# DC_MOTOR_DRIVER_V2_0.net
KiCad netlist of a schematic drawn in EasyEDA Pro
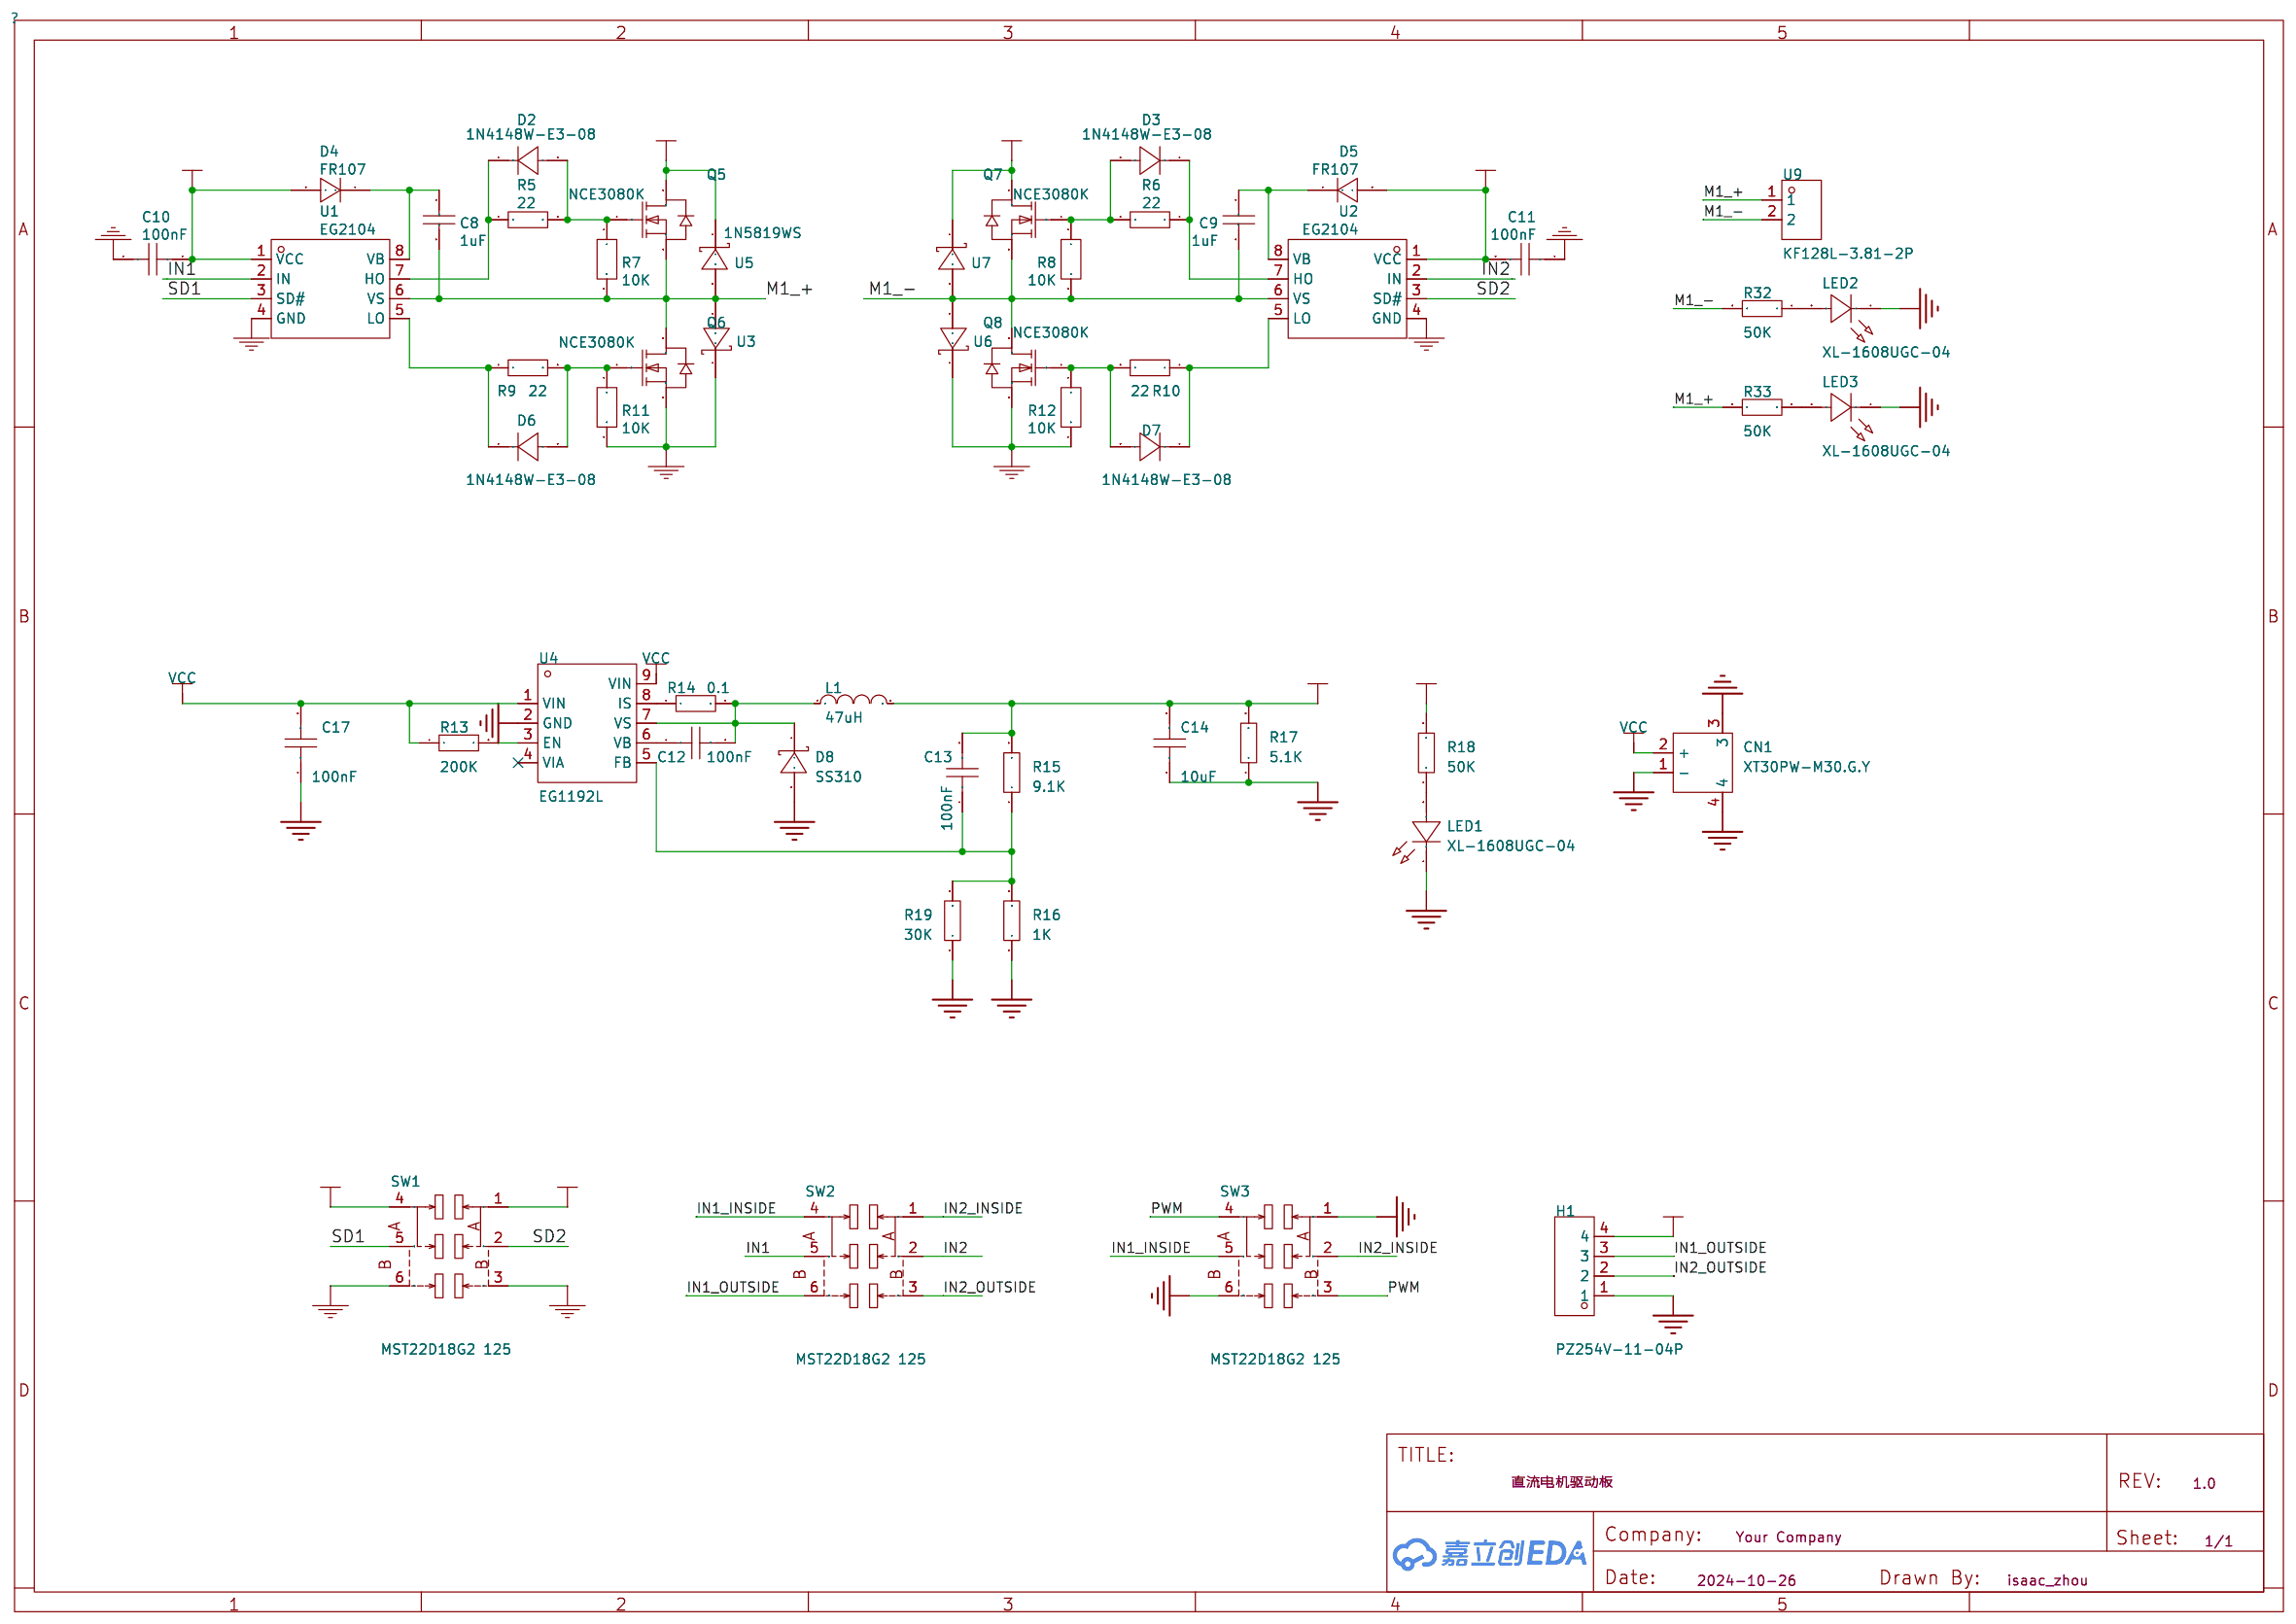
[diagram p0: Sheet_1]
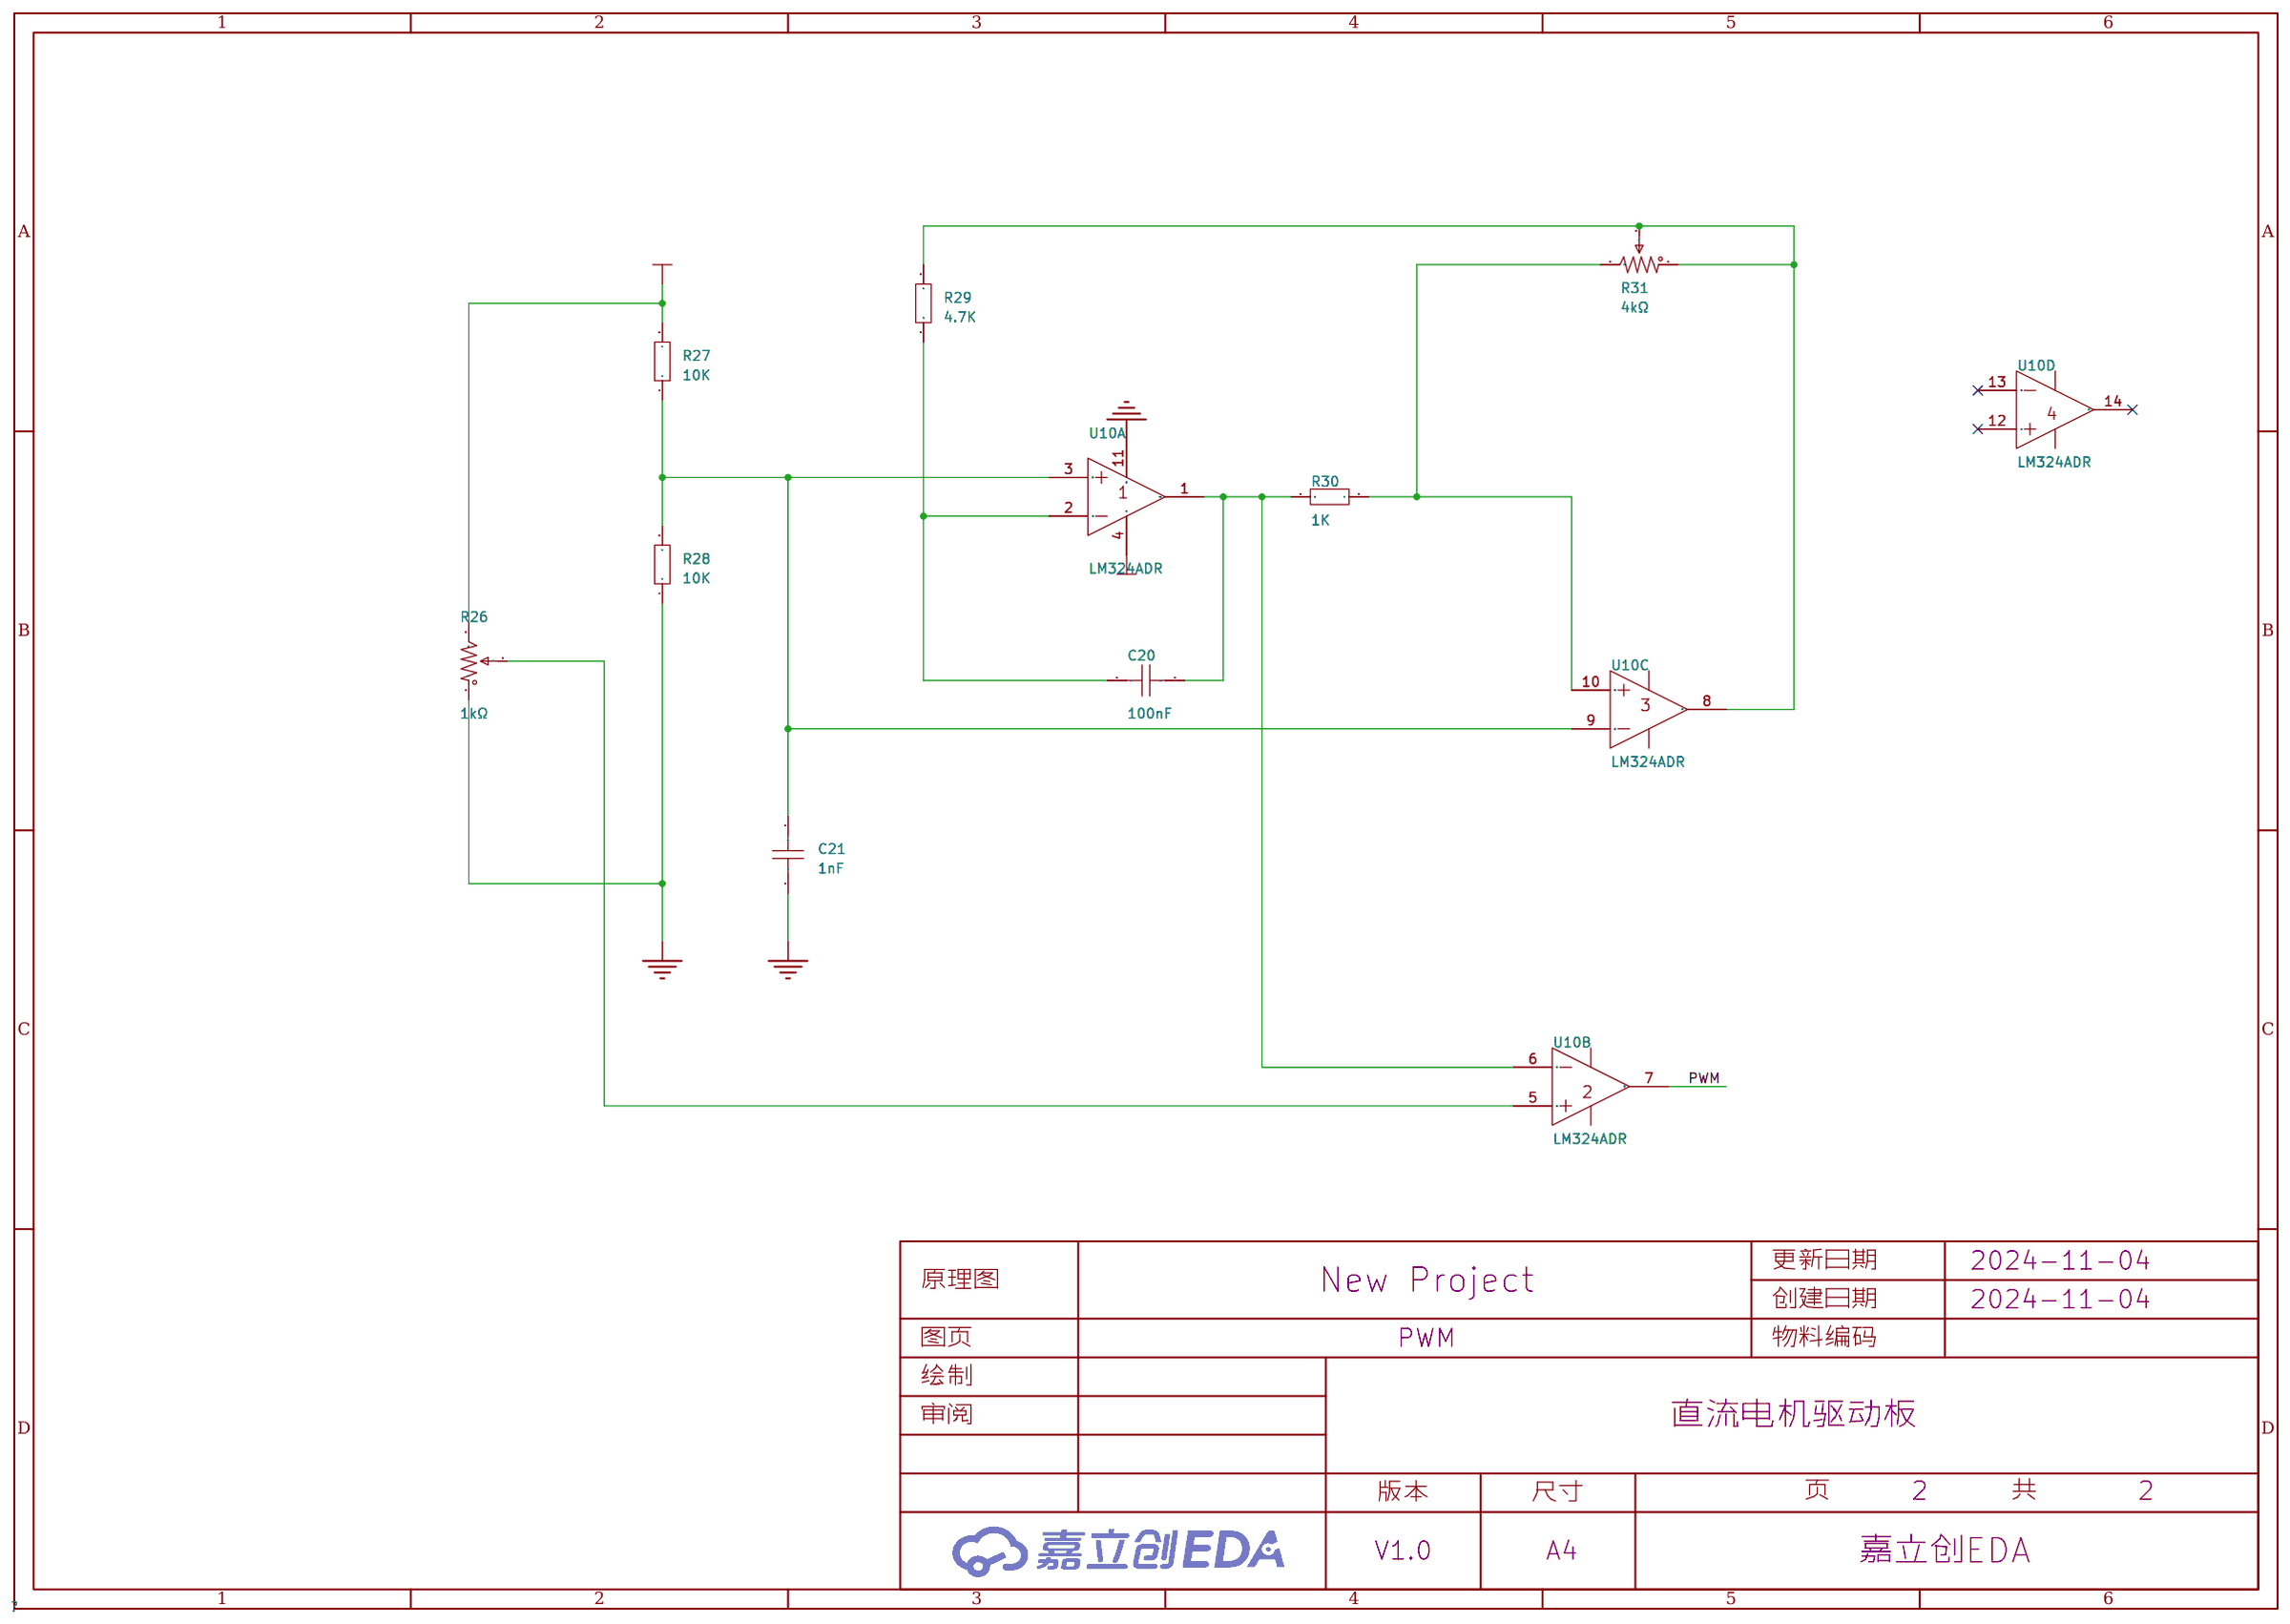
[diagram p1: PWM]

(export (version "E")
  (design (tool "Eeschema 10.0.6"))
  (components
    (comp (ref "C8")
      (value "1uF")
      (fields (field (name "Manufacturer Part") "CL21F105ZOFNNNE") (field (name "Manufacturer") "SAMSUNG"))
      (libsource (lib "easyedapro") (part "1uF"))
    )
    (comp (ref "C9")
      (value "1uF")
      (fields (field (name "Manufacturer Part") "CL21F105ZOFNNNE") (field (name "Manufacturer") "SAMSUNG"))
      (libsource (lib "easyedapro") (part "1uF"))
    )
    (comp (ref "C10")
      (value "100nF")
      (fields (field (name "Manufacturer Part") "C0805C104K4RAC7800") (field (name "Manufacturer") "KEMET"))
      (libsource (lib "") (part "100nF_1"))
    )
    (comp (ref "C11")
      (value "100nF")
      (fields (field (name "Manufacturer Part") "C0805C104K4RAC7800") (field (name "Manufacturer") "KEMET"))
      (libsource (lib "easyedapro") (part "100nF"))
    )
    (comp (ref "C12")
      (value "100nF")
      (footprint "easyedapro:C0603")
      (libsource (lib "easyedapro") (part "CapAcitance"))
    )
    (comp (ref "C13")
      (value "100nF")
      (footprint "easyedapro:C0603")
      (libsource (lib "easyedapro") (part "CapAcitance"))
    )
    (comp (ref "C14")
      (value "10uF")
      (footprint "easyedapro:C0603")
      (libsource (lib "easyedapro") (part "CapAcitance"))
    )
    (comp (ref "C17")
      (value "100nF")
      (footprint "easyedapro:C0603")
      (libsource (lib "easyedapro") (part "CapAcitance"))
    )
    (comp (ref "CN1")
      (value "XT30PW-M30.G.Y")
      (footprint "easyedapro:CONN-TH_XT30PW-M")
      (description "类别:-;类型1:-;")
      (fields (field (name "Manufacturer") "AMASS(艾迈斯)"))
      (libsource (lib "easyedapro") (part "XT30PW-M"))
    )
    (comp (ref "D2")
      (value "1N4148W-E3-08")
      (fields (field (name "Manufacturer") "VISHAY(威世)"))
      (libsource (lib "easyedapro") (part "1N4148W_C727110"))
    )
    (comp (ref "D3")
      (value "1N4148W-E3-08")
      (fields (field (name "Manufacturer") "VISHAY(威世)"))
      (libsource (lib "") (part "1N4148W_C727110_1"))
    )
    (comp (ref "D4")
      (value "FR107")
      (fields (field (name "Manufacturer") "Slkor(萨科微)"))
      (libsource (lib "") (part "FR107_C511885_1"))
    )
    (comp (ref "D5")
      (value "FR107")
      (fields (field (name "Manufacturer") "Slkor(萨科微)"))
      (libsource (lib "easyedapro") (part "FR107_C511885"))
    )
    (comp (ref "D6")
      (value "1N4148W-E3-08")
      (fields (field (name "Manufacturer") "VISHAY(威世)"))
      (libsource (lib "easyedapro") (part "1N4148W_C727110"))
    )
    (comp (ref "D7")
      (value "1N4148W-E3-08")
      (fields (field (name "Manufacturer") "VISHAY(威世)"))
      (libsource (lib "") (part "1N4148W_C727110_1"))
    )
    (comp (ref "D8")
      (value "SS310")
      (footprint "easyedapro:SMA_L4.3-W2.6-LS5.2-RD")
      (description "二极管配置:独立式;正向压降(Vf):850mV@3A;直流反向耐压(Vr):100V;整流电流:3A;")
      (fields (field (name "Manufacturer") "MDD(辰达半导体)"))
      (libsource (lib "easyedapro") (part "SS310"))
    )
    (comp (ref "H1")
      (value "PZ254V-11-04P")
      (footprint "easyedapro:HDR-TH_4P-P2.54-V-M")
      (fields (field (name "Manufacturer") "XFCN(兴飞)"))
      (libsource (lib "easyedapro") (part "PZ254V-11-04P_C2691448"))
    )
    (comp (ref "L1")
      (value "47uH")
      (fields (field (name "Manufacturer Part") "CKST0603-47uH/M") (field (name "Manufacturer") "CENKER(岑科)"))
      (libsource (lib "easyedapro") (part "SDFL1608S100KTF"))
    )
    (comp (ref "LED1")
      (value "XL-1608UGC-04")
      (footprint "easyedapro:LED0603-RD_GREEN")
      (fields (field (name "Manufacturer") "XINGLIGHT(成兴光)"))
      (libsource (lib "easyedapro") (part "XL-1608UGC-04"))
    )
    (comp (ref "LED2")
      (value "XL-1608UGC-04")
      (footprint "easyedapro:LED0603-RD_GREEN")
      (fields (field (name "Manufacturer") "XINGLIGHT(成兴光)"))
      (libsource (lib "easyedapro") (part "XL-1608UGC-04"))
    )
    (comp (ref "LED3")
      (value "XL-1608UGC-04")
      (footprint "easyedapro:LED0603-RD_GREEN")
      (fields (field (name "Manufacturer") "XINGLIGHT(成兴光)"))
      (libsource (lib "easyedapro") (part "XL-1608UGC-04"))
    )
    (comp (ref "Q5")
      (value "NCE3080K")
      (footprint "easyedapro:TO-252-2_L6.6-W6.1-P4.57-LS9.9-TL-CW")
      (fields (field (name "Manufacturer") "NCE(无锡新洁能)"))
      (libsource (lib "easyedapro") (part "NCE3080K"))
    )
    (comp (ref "Q6")
      (value "NCE3080K")
      (footprint "easyedapro:TO-252-2_L6.6-W6.1-P4.57-LS9.9-TL-CW")
      (fields (field (name "Manufacturer") "NCE(无锡新洁能)"))
      (libsource (lib "easyedapro") (part "NCE3080K"))
    )
    (comp (ref "Q7")
      (value "NCE3080K")
      (footprint "easyedapro:TO-252-2_L6.6-W6.1-P4.57-LS9.9-TL-CW")
      (fields (field (name "Manufacturer") "NCE(无锡新洁能)"))
      (libsource (lib "easyedapro") (part "NCE3080K"))
    )
    (comp (ref "Q8")
      (value "NCE3080K")
      (footprint "easyedapro:TO-252-2_L6.6-W6.1-P4.57-LS9.9-TL-CW")
      (fields (field (name "Manufacturer") "NCE(无锡新洁能)"))
      (libsource (lib "easyedapro") (part "NCE3080K"))
    )
    (comp (ref "R5")
      (value "22")
      (fields (field (name "Manufacturer Part") "0805W8F220JT5E") (field (name "Manufacturer") "UniOhm"))
      (libsource (lib "easyedapro") (part "22"))
    )
    (comp (ref "R6")
      (value "22")
      (fields (field (name "Manufacturer Part") "0805W8F220JT5E") (field (name "Manufacturer") "UniOhm"))
      (libsource (lib "") (part "22_1"))
    )
    (comp (ref "R7")
      (value "10K")
      (fields
        (field (name "Manufacturer Part") "0805W8F1002T5E")
        (field (name "Manufacturer") "Uniroyal Elec")
      )
      (libsource (lib "easyedapro") (part "10K"))
    )
    (comp (ref "R8")
      (value "10K")
      (fields
        (field (name "Manufacturer Part") "0805W8F1002T5E")
        (field (name "Manufacturer") "Uniroyal Elec")
      )
      (libsource (lib "easyedapro") (part "10K"))
    )
    (comp (ref "R9")
      (value "22")
      (fields (field (name "Manufacturer Part") "0805W8F220JT5E") (field (name "Manufacturer") "UniOhm"))
      (libsource (lib "easyedapro") (part "22"))
    )
    (comp (ref "R10")
      (value "22")
      (fields (field (name "Manufacturer Part") "0805W8F220JT5E") (field (name "Manufacturer") "UniOhm"))
      (libsource (lib "") (part "22_1"))
    )
    (comp (ref "R11")
      (value "10K")
      (fields
        (field (name "Manufacturer Part") "0805W8F1002T5E")
        (field (name "Manufacturer") "Uniroyal Elec")
      )
      (libsource (lib "easyedapro") (part "10K"))
    )
    (comp (ref "R12")
      (value "10K")
      (fields
        (field (name "Manufacturer Part") "0805W8F1002T5E")
        (field (name "Manufacturer") "Uniroyal Elec")
      )
      (libsource (lib "easyedapro") (part "10K"))
    )
    (comp (ref "R13")
      (value "200K")
      (footprint "easyedapro:R0603")
      (libsource (lib "easyedapro") (part "电阻"))
    )
    (comp (ref "R14") (value "0.1") (footprint "easyedapro:R0603") (libsource (lib "easyedapro") (part "电阻")))
    (comp (ref "R15")
      (value "9.1K")
      (footprint "easyedapro:R0603")
      (libsource (lib "easyedapro") (part "电阻"))
    )
    (comp (ref "R16") (value "1K") (footprint "easyedapro:R0603") (libsource (lib "easyedapro") (part "电阻")))
    (comp (ref "R17")
      (value "5.1K")
      (footprint "easyedapro:R0603")
      (libsource (lib "easyedapro") (part "电阻"))
    )
    (comp (ref "R18") (value "50K") (footprint "easyedapro:R0603") (libsource (lib "easyedapro") (part "电阻")))
    (comp (ref "R19") (value "30K") (footprint "easyedapro:R0603") (libsource (lib "easyedapro") (part "电阻")))
    (comp (ref "R32") (value "50K") (footprint "easyedapro:R0603") (libsource (lib "easyedapro") (part "电阻")))
    (comp (ref "R33") (value "50K") (footprint "easyedapro:R0603") (libsource (lib "easyedapro") (part "电阻")))
    (comp (ref "SW1")
      (value "MST22D18G2 125")
      (footprint "easyedapro:SW-SMD_MST22D18G2")
      (description "电路结构:双刀双掷;安装方式:立贴;开关颜色:黑色;额定电流(DC):100mA;额定电压(DC):12V;机械寿命:1万次;")
      (fields (field (name "Manufacturer") "SHOU HAN(首韩)"))
      (libsource (lib "easyedapro") (part "MST22D18G2 125"))
    )
    (comp (ref "SW2")
      (value "MST22D18G2 125")
      (footprint "easyedapro:SW-SMD_MST22D18G2")
      (description "电路结构:双刀双掷;安装方式:立贴;开关颜色:黑色;额定电流(DC):100mA;额定电压(DC):12V;机械寿命:1万次;")
      (fields (field (name "Manufacturer") "SHOU HAN(首韩)"))
      (libsource (lib "easyedapro") (part "MST22D18G2 125"))
    )
    (comp (ref "SW3")
      (value "MST22D18G2 125")
      (footprint "easyedapro:SW-SMD_MST22D18G2")
      (description "电路结构:双刀双掷;安装方式:立贴;开关颜色:黑色;额定电流(DC):100mA;额定电压(DC):12V;机械寿命:1万次;")
      (fields (field (name "Manufacturer") "SHOU HAN(首韩)"))
      (libsource (lib "easyedapro") (part "MST22D18G2 125"))
    )
    (comp (ref "U1")
      (value "EG2104")
      (fields (field (name "Manufacturer") "EG(屹晶微)"))
      (libsource (lib "") (part "EG2104_1"))
    )
    (comp (ref "U2")
      (value "EG2104")
      (fields (field (name "Manufacturer") "EG(屹晶微)"))
      (libsource (lib "easyedapro") (part "EG2104"))
    )
    (comp (ref "U3")
      (value "1N5819WS")
      (fields (field (name "Manufacturer") "Hottech(合科泰)"))
      (libsource (lib "easyedapro") (part "1N5819HW-MS"))
    )
    (comp (ref "U4")
      (value "EG1192L")
      (footprint "easyedapro:ESOP-8_L4.9-W3.9-P1.27-LS6.0-BL-EP")
      (description "零功耗使能降压 DCDC 电源芯片")
      (fields (field (name "Manufacturer") "EG(屹晶微)"))
      (libsource (lib "easyedapro") (part "EG1192L"))
    )
    (comp (ref "U5")
      (value "1N5819WS")
      (fields (field (name "Manufacturer") "Hottech(合科泰)"))
      (libsource (lib "easyedapro") (part "1N5819"))
    )
    (comp (ref "U6")
      (value "1N5819WS")
      (fields (field (name "Manufacturer") "Hottech(合科泰)"))
      (libsource (lib "easyedapro") (part "1N5819HW-MS"))
    )
    (comp (ref "U7")
      (value "1N5819WS")
      (fields (field (name "Manufacturer") "Hottech(合科泰)"))
      (libsource (lib "easyedapro") (part "1N5819HW-MS"))
    )
    (comp (ref "U9")
      (value "KF128L-3.81-2P")
      (footprint "easyedapro:CONN-TH_P3.81_KF128L-3.81-2P")
      (fields (field (name "Manufacturer") "KEFA(科发)"))
      (libsource (lib "easyedapro") (part "KF128L-3.81-2P"))
    )
    (comp (ref "C20")
      (value "100nF")
      (footprint "easyedapro:C0603")
      (libsource (lib "easyedapro") (part "CapAcitance"))
    )
    (comp (ref "C21")
      (value "1nF")
      (footprint "easyedapro:C0603")
      (libsource (lib "easyedapro") (part "CapAcitance"))
    )
    (comp (ref "R26")
      (value "1kΩ")
      (footprint "easyedapro:RES-ADJ-TH_3362P")
      (description "阻值:1kΩ;精度:±10%;")
      (fields (field (name "Manufacturer Part") "3362P-1-102") (field (name "Manufacturer") "BOCHEN(博晨)"))
      (libsource (lib "easyedapro") (part "3362P-1-102"))
    )
    (comp (ref "R27") (value "10K") (footprint "easyedapro:R0603") (libsource (lib "easyedapro") (part "电阻")))
    (comp (ref "R28") (value "10K") (footprint "easyedapro:R0603") (libsource (lib "easyedapro") (part "电阻")))
    (comp (ref "R29")
      (value "4.7K")
      (footprint "easyedapro:R0603")
      (libsource (lib "easyedapro") (part "电阻"))
    )
    (comp (ref "R30") (value "1K") (footprint "easyedapro:R0603") (libsource (lib "easyedapro") (part "电阻")))
    (comp (ref "R31")
      (value "4kΩ")
      (footprint "easyedapro:RES-ADJ-TH_3362P")
      (description "阻值:1kΩ;精度:±10%;")
      (fields (field (name "Manufacturer Part") "3362P-1-102") (field (name "Manufacturer") "BOCHEN(博晨)"))
      (libsource (lib "easyedapro") (part "3362P-1-102"))
    )
    (comp (ref "U10")
      (value "LM324ADR")
      (footprint "easyedapro:SOP-14_L8.6-W3.9-P1.27-LS6.0-BL")
      (fields (field (name "Manufacturer") "UMW(友台半导体)"))
      (libsource (lib "easyedapro") (part "LM324ADR_C2837469"))
    )
  )
  (nets
    (net (code "1") (name "12V") (class "Default")
      (node (ref "C10") (pin "2") (pinfunction "2_2") (pintype "unspecified"))
      (node (ref "C11") (pin "2") (pinfunction "2_2") (pintype "unspecified"))
      (node (ref "C13") (pin "2") (pinfunction "2_2") (pintype "input"))
      (node (ref "C14") (pin "2") (pinfunction "2_2") (pintype "input"))
      (node (ref "D4") (pin "2") (pinfunction "A_2") (pintype "unspecified"))
      (node (ref "D5") (pin "2") (pinfunction "A_2") (pintype "unspecified"))
      (node (ref "H1") (pin "4") (pinfunction "4_4") (pintype "unspecified"))
      (node (ref "L1") (pin "2") (pinfunction "2_2") (pintype "unspecified"))
      (node (ref "Q5") (pin "2") (pinfunction "D_2") (pintype "unspecified"))
      (node (ref "Q7") (pin "2") (pinfunction "D_2") (pintype "unspecified"))
      (node (ref "R15") (pin "2") (pinfunction "2_2") (pintype "input"))
      (node (ref "R17") (pin "2") (pinfunction "2_2") (pintype "input"))
      (node (ref "R18") (pin "2") (pinfunction "2_2") (pintype "input"))
      (node (ref "R26") (pin "3") (pinfunction "3_3") (pintype "unspecified"))
      (node (ref "R27") (pin "2") (pinfunction "2_2") (pintype "input"))
      (node (ref "SW1") (pin "1") (pinfunction "1_1") (pintype "unspecified"))
      (node (ref "SW1") (pin "4") (pinfunction "4_4") (pintype "unspecified"))
      (node (ref "U1") (pin "1") (pinfunction "VCC_1") (pintype "unspecified"))
      (node (ref "U10") (pin "4") (pinfunction "VCC_4") (pintype "unspecified"))
      (node (ref "U2") (pin "1") (pinfunction "VCC_1") (pintype "unspecified"))
      (node (ref "U5") (pin "1") (pinfunction "K_1") (pintype "unspecified"))
      (node (ref "U7") (pin "1") (pinfunction "K_1") (pintype "unspecified"))
    )
    (net (code "2") (name "GND") (class "Default")
      (node (ref "C10") (pin "1") (pinfunction "1_1") (pintype "unspecified"))
      (node (ref "C11") (pin "1") (pinfunction "1_1") (pintype "unspecified"))
      (node (ref "C14") (pin "1") (pinfunction "1_1") (pintype "input"))
      (node (ref "C17") (pin "1") (pinfunction "1_1") (pintype "input"))
      (node (ref "C21") (pin "1") (pinfunction "1_1") (pintype "input"))
      (node (ref "CN1") (pin "1") (pinfunction "-_1") (pintype "unspecified"))
      (node (ref "CN1") (pin "3") (pinfunction "3_3") (pintype "unspecified"))
      (node (ref "CN1") (pin "4") (pinfunction "4_4") (pintype "unspecified"))
      (node (ref "D8") (pin "2") (pinfunction "A_2") (pintype "unspecified"))
      (node (ref "H1") (pin "1") (pinfunction "1_1") (pintype "unspecified"))
      (node (ref "LED1") (pin "1") (pinfunction "K_1") (pintype "unspecified"))
      (node (ref "LED2") (pin "1") (pinfunction "K_1") (pintype "unspecified"))
      (node (ref "LED3") (pin "1") (pinfunction "K_1") (pintype "unspecified"))
      (node (ref "Q6") (pin "3") (pinfunction "S_3") (pintype "unspecified"))
      (node (ref "Q8") (pin "3") (pinfunction "S_3") (pintype "unspecified"))
      (node (ref "R11") (pin "2") (pinfunction "2_2") (pintype "unspecified"))
      (node (ref "R12") (pin "2") (pinfunction "2_2") (pintype "unspecified"))
      (node (ref "R16") (pin "1") (pinfunction "1_1") (pintype "input"))
      (node (ref "R17") (pin "1") (pinfunction "1_1") (pintype "input"))
      (node (ref "R19") (pin "1") (pinfunction "1_1") (pintype "input"))
      (node (ref "R26") (pin "1") (pinfunction "1_1") (pintype "unspecified"))
      (node (ref "R28") (pin "1") (pinfunction "1_1") (pintype "input"))
      (node (ref "SW1") (pin "3") (pinfunction "3_3") (pintype "unspecified"))
      (node (ref "SW1") (pin "6") (pinfunction "6_6") (pintype "unspecified"))
      (node (ref "SW3") (pin "1") (pinfunction "1_1") (pintype "unspecified"))
      (node (ref "SW3") (pin "6") (pinfunction "6_6") (pintype "unspecified"))
      (node (ref "U1") (pin "4") (pinfunction "GND_4") (pintype "unspecified"))
      (node (ref "U10") (pin "11") (pinfunction "GND_11") (pintype "unspecified"))
      (node (ref "U2") (pin "4") (pinfunction "GND_4") (pintype "unspecified"))
      (node (ref "U3") (pin "1") (pinfunction "K_1") (pintype "unspecified"))
      (node (ref "U4") (pin "2") (pinfunction "GND_2") (pintype "unspecified"))
      (node (ref "U6") (pin "1") (pinfunction "K_1") (pintype "unspecified"))
    )
    (net (code "3") (name "IN1") (class "Default")
      (node (ref "SW2") (pin "5") (pinfunction "5_5") (pintype "unspecified"))
      (node (ref "U1") (pin "2") (pinfunction "IN_2") (pintype "unspecified"))
    )
    (net (code "4") (name "IN1_INSIDE") (class "Default")
      (node (ref "SW2") (pin "4") (pinfunction "4_4") (pintype "unspecified"))
      (node (ref "SW3") (pin "5") (pinfunction "5_5") (pintype "unspecified"))
    )
    (net (code "5") (name "IN1_OUTSIDE") (class "Default")
      (node (ref "H1") (pin "3") (pinfunction "3_3") (pintype "unspecified"))
      (node (ref "SW2") (pin "6") (pinfunction "6_6") (pintype "unspecified"))
    )
    (net (code "6") (name "IN2") (class "Default")
      (node (ref "SW2") (pin "2") (pinfunction "2_2") (pintype "unspecified"))
      (node (ref "U2") (pin "2") (pinfunction "IN_2") (pintype "unspecified"))
    )
    (net (code "7") (name "IN2_INSIDE") (class "Default")
      (node (ref "SW2") (pin "1") (pinfunction "1_1") (pintype "unspecified"))
      (node (ref "SW3") (pin "2") (pinfunction "2_2") (pintype "unspecified"))
    )
    (net (code "8") (name "IN2_OUTSIDE") (class "Default")
      (node (ref "H1") (pin "2") (pinfunction "2_2") (pintype "unspecified"))
      (node (ref "SW2") (pin "3") (pinfunction "3_3") (pintype "unspecified"))
    )
    (net (code "9") (name "M1_+") (class "Default")
      (node (ref "C8") (pin "2") (pinfunction "2_2") (pintype "input"))
      (node (ref "Q5") (pin "3") (pinfunction "S_3") (pintype "unspecified"))
      (node (ref "Q6") (pin "2") (pinfunction "D_2") (pintype "unspecified"))
      (node (ref "R33") (pin "2") (pinfunction "2_2") (pintype "input"))
      (node (ref "R7") (pin "2") (pinfunction "2_2") (pintype "unspecified"))
      (node (ref "U1") (pin "6") (pinfunction "VS_6") (pintype "unspecified"))
      (node (ref "U3") (pin "2") (pinfunction "A_2") (pintype "unspecified"))
      (node (ref "U5") (pin "2") (pinfunction "A_2") (pintype "unspecified"))
      (node (ref "U9") (pin "1") (pinfunction "1_1") (pintype "unspecified"))
    )
    (net (code "10") (name "M1_-") (class "Default")
      (node (ref "C9") (pin "2") (pinfunction "2_2") (pintype "input"))
      (node (ref "Q7") (pin "3") (pinfunction "S_3") (pintype "unspecified"))
      (node (ref "Q8") (pin "2") (pinfunction "D_2") (pintype "unspecified"))
      (node (ref "R32") (pin "2") (pinfunction "2_2") (pintype "input"))
      (node (ref "R8") (pin "2") (pinfunction "2_2") (pintype "unspecified"))
      (node (ref "U2") (pin "6") (pinfunction "VS_6") (pintype "unspecified"))
      (node (ref "U6") (pin "2") (pinfunction "A_2") (pintype "unspecified"))
      (node (ref "U7") (pin "2") (pinfunction "A_2") (pintype "unspecified"))
      (node (ref "U9") (pin "2") (pinfunction "2_2") (pintype "unspecified"))
    )
    (net (code "11") (name "Net-(D2-A)") (class "Default")
      (node (ref "D2") (pin "2") (pinfunction "A_2") (pintype "unspecified"))
      (node (ref "Q5") (pin "1") (pinfunction "G_1") (pintype "unspecified"))
      (node (ref "R5") (pin "2") (pinfunction "2_2") (pintype "input"))
      (node (ref "R7") (pin "1") (pinfunction "1_1") (pintype "unspecified"))
    )
    (net (code "12") (name "Net-(D2-K)") (class "Default")
      (node (ref "D2") (pin "1") (pinfunction "K_1") (pintype "unspecified"))
      (node (ref "R5") (pin "1") (pinfunction "1_1") (pintype "input"))
      (node (ref "U1") (pin "7") (pinfunction "HO_7") (pintype "unspecified"))
    )
    (net (code "13") (name "Net-(D3-A)") (class "Default")
      (node (ref "D3") (pin "2") (pinfunction "A_2") (pintype "unspecified"))
      (node (ref "Q7") (pin "1") (pinfunction "G_1") (pintype "unspecified"))
      (node (ref "R6") (pin "2") (pinfunction "2_2") (pintype "input"))
      (node (ref "R8") (pin "1") (pinfunction "1_1") (pintype "unspecified"))
    )
    (net (code "14") (name "Net-(D3-K)") (class "Default")
      (node (ref "D3") (pin "1") (pinfunction "K_1") (pintype "unspecified"))
      (node (ref "R6") (pin "1") (pinfunction "1_1") (pintype "input"))
      (node (ref "U2") (pin "7") (pinfunction "HO_7") (pintype "unspecified"))
    )
    (net (code "15") (name "Net-(D4-K)") (class "Default")
      (node (ref "C8") (pin "1") (pinfunction "1_1") (pintype "input"))
      (node (ref "D4") (pin "1") (pinfunction "K_1") (pintype "unspecified"))
      (node (ref "U1") (pin "8") (pinfunction "VB_8") (pintype "unspecified"))
    )
    (net (code "16") (name "Net-(D5-K)") (class "Default")
      (node (ref "C9") (pin "1") (pinfunction "1_1") (pintype "input"))
      (node (ref "D5") (pin "1") (pinfunction "K_1") (pintype "unspecified"))
      (node (ref "U2") (pin "8") (pinfunction "VB_8") (pintype "unspecified"))
    )
    (net (code "17") (name "Net-(D6-A)") (class "Default")
      (node (ref "D6") (pin "2") (pinfunction "A_2") (pintype "unspecified"))
      (node (ref "Q6") (pin "1") (pinfunction "G_1") (pintype "unspecified"))
      (node (ref "R11") (pin "1") (pinfunction "1_1") (pintype "unspecified"))
      (node (ref "R9") (pin "2") (pinfunction "2_2") (pintype "input"))
    )
    (net (code "18") (name "Net-(D6-K)") (class "Default")
      (node (ref "D6") (pin "1") (pinfunction "K_1") (pintype "unspecified"))
      (node (ref "R9") (pin "1") (pinfunction "1_1") (pintype "input"))
      (node (ref "U1") (pin "5") (pinfunction "LO_5") (pintype "unspecified"))
    )
    (net (code "19") (name "Net-(D7-A)") (class "Default")
      (node (ref "D7") (pin "2") (pinfunction "A_2") (pintype "unspecified"))
      (node (ref "Q8") (pin "1") (pinfunction "G_1") (pintype "unspecified"))
      (node (ref "R10") (pin "2") (pinfunction "2_2") (pintype "input"))
      (node (ref "R12") (pin "1") (pinfunction "1_1") (pintype "unspecified"))
    )
    (net (code "20") (name "Net-(D7-K)") (class "Default")
      (node (ref "D7") (pin "1") (pinfunction "K_1") (pintype "unspecified"))
      (node (ref "R10") (pin "1") (pinfunction "1_1") (pintype "input"))
      (node (ref "U2") (pin "5") (pinfunction "LO_5") (pintype "unspecified"))
    )
    (net (code "21") (name "Net-(D8-K)") (class "Default")
      (node (ref "C12") (pin "2") (pinfunction "2_2") (pintype "input"))
      (node (ref "D8") (pin "1") (pinfunction "K_1") (pintype "unspecified"))
      (node (ref "L1") (pin "1") (pinfunction "1_1") (pintype "unspecified"))
      (node (ref "R14") (pin "2") (pinfunction "2_2") (pintype "input"))
      (node (ref "U4") (pin "7") (pinfunction "VS_7") (pintype "unspecified"))
    )
    (net (code "22") (name "Net-(LED1-A)") (class "Default")
      (node (ref "LED1") (pin "2") (pinfunction "A_2") (pintype "unspecified"))
      (node (ref "R18") (pin "1") (pinfunction "1_1") (pintype "input"))
    )
    (net (code "23") (name "Net-(LED2-A)") (class "Default")
      (node (ref "LED2") (pin "2") (pinfunction "A_2") (pintype "unspecified"))
      (node (ref "R32") (pin "1") (pinfunction "1_1") (pintype "input"))
    )
    (net (code "24") (name "Net-(LED3-A)") (class "Default")
      (node (ref "LED3") (pin "2") (pinfunction "A_2") (pintype "unspecified"))
      (node (ref "R33") (pin "1") (pinfunction "1_1") (pintype "input"))
    )
    (net (code "25") (name "Net-(U4-EN)") (class "Default")
      (node (ref "R13") (pin "2") (pinfunction "2_2") (pintype "input"))
      (node (ref "U4") (pin "3") (pinfunction "EN_3") (pintype "unspecified"))
    )
    (net (code "26") (name "Net-(U4-FB)") (class "Default")
      (node (ref "C13") (pin "1") (pinfunction "1_1") (pintype "input"))
      (node (ref "R15") (pin "1") (pinfunction "1_1") (pintype "input"))
      (node (ref "R16") (pin "2") (pinfunction "2_2") (pintype "input"))
      (node (ref "R19") (pin "2") (pinfunction "2_2") (pintype "input"))
      (node (ref "U4") (pin "5") (pinfunction "FB_5") (pintype "unspecified"))
    )
    (net (code "27") (name "Net-(U4-IS)") (class "Default")
      (node (ref "R14") (pin "1") (pinfunction "1_1") (pintype "input"))
      (node (ref "U4") (pin "8") (pinfunction "IS_8") (pintype "unspecified"))
    )
    (net (code "28") (name "Net-(U4-VB)") (class "Default")
      (node (ref "C12") (pin "1") (pinfunction "1_1") (pintype "input"))
      (node (ref "U4") (pin "6") (pinfunction "VB_6") (pintype "unspecified"))
    )
    (net (code "29") (name "Net-(U10A-1IN+)") (class "Default")
      (node (ref "C21") (pin "2") (pinfunction "2_2") (pintype "input"))
      (node (ref "R27") (pin "1") (pinfunction "1_1") (pintype "input"))
      (node (ref "R28") (pin "2") (pinfunction "2_2") (pintype "input"))
      (node (ref "U10") (pin "3") (pinfunction "1IN+_3") (pintype "unspecified"))
      (node (ref "U10") (pin "9") (pinfunction "3IN-_9") (pintype "unspecified"))
    )
    (net (code "30") (name "Net-(U10A-1IN-)") (class "Default")
      (node (ref "C20") (pin "1") (pinfunction "1_1") (pintype "input"))
      (node (ref "R29") (pin "1") (pinfunction "1_1") (pintype "input"))
      (node (ref "U10") (pin "2") (pinfunction "1IN-_2") (pintype "unspecified"))
    )
    (net (code "31") (name "Net-(U10A-1OUT)") (class "Default")
      (node (ref "C20") (pin "2") (pinfunction "2_2") (pintype "input"))
      (node (ref "R30") (pin "2") (pinfunction "2_2") (pintype "input"))
      (node (ref "U10") (pin "1") (pinfunction "1OUT_1") (pintype "unspecified"))
      (node (ref "U10") (pin "6") (pinfunction "2IN-_6") (pintype "unspecified"))
    )
    (net (code "32") (name "Net-(U10B-2IN+)") (class "Default")
      (node (ref "R26") (pin "2") (pinfunction "2_2") (pintype "unspecified"))
      (node (ref "U10") (pin "5") (pinfunction "2IN+_5") (pintype "unspecified"))
    )
    (net (code "33") (name "Net-(U10C-3IN+)") (class "Default")
      (node (ref "R30") (pin "1") (pinfunction "1_1") (pintype "input"))
      (node (ref "R31") (pin "3") (pinfunction "3_3") (pintype "unspecified"))
      (node (ref "U10") (pin "10") (pinfunction "3IN+_10") (pintype "unspecified"))
    )
    (net (code "34") (name "Net-(U10C-3OUT)") (class "Default")
      (node (ref "R29") (pin "2") (pinfunction "2_2") (pintype "input"))
      (node (ref "R31") (pin "1") (pinfunction "1_1") (pintype "unspecified"))
      (node (ref "R31") (pin "2") (pinfunction "2_2") (pintype "unspecified"))
      (node (ref "U10") (pin "8") (pinfunction "3OUT_8") (pintype "unspecified"))
    )
    (net (code "35") (name "PWM") (class "Default")
      (node (ref "SW3") (pin "3") (pinfunction "3_3") (pintype "unspecified"))
      (node (ref "SW3") (pin "4") (pinfunction "4_4") (pintype "unspecified"))
      (node (ref "U10") (pin "7") (pinfunction "2OUT_7") (pintype "unspecified"))
    )
    (net (code "36") (name "SD1") (class "Default")
      (node (ref "SW1") (pin "5") (pinfunction "5_5") (pintype "unspecified"))
      (node (ref "U1") (pin "3") (pinfunction "SD#_3") (pintype "unspecified"))
    )
    (net (code "37") (name "SD2") (class "Default")
      (node (ref "SW1") (pin "2") (pinfunction "2_2") (pintype "unspecified"))
      (node (ref "U2") (pin "3") (pinfunction "SD#_3") (pintype "unspecified"))
    )
    (net (code "38") (name "VCC") (class "Default")
      (node (ref "C17") (pin "2") (pinfunction "2_2") (pintype "input"))
      (node (ref "CN1") (pin "2") (pinfunction "+_2") (pintype "unspecified"))
      (node (ref "R13") (pin "1") (pinfunction "1_1") (pintype "input"))
      (node (ref "U4") (pin "1") (pinfunction "VIN_1") (pintype "unspecified"))
      (node (ref "U4") (pin "9") (pinfunction "VIN_9") (pintype "unspecified"))
    )
    (net (code "39") (name "unconnected-(U4-VIA-Pad4)") (class "Default")
      (node (ref "U4") (pin "4") (pinfunction "VIA_4") (pintype "unspecified+no_connect"))
    )
    (net (code "40") (name "unconnected-(U10D-4IN+-Pad12)") (class "Default")
      (node (ref "U10") (pin "12") (pinfunction "4IN+_12") (pintype "unspecified+no_connect"))
    )
    (net (code "41") (name "unconnected-(U10D-4IN--Pad13)") (class "Default")
      (node (ref "U10") (pin "13") (pinfunction "4IN-_13") (pintype "unspecified+no_connect"))
    )
    (net (code "42") (name "unconnected-(U10D-4OUT-Pad14)") (class "Default")
      (node (ref "U10") (pin "14") (pinfunction "4OUT_14") (pintype "unspecified+no_connect"))
    )
  )
)
